# PoEpi_v2.net
KiCad netlist of a schematic drawn in EAGLE
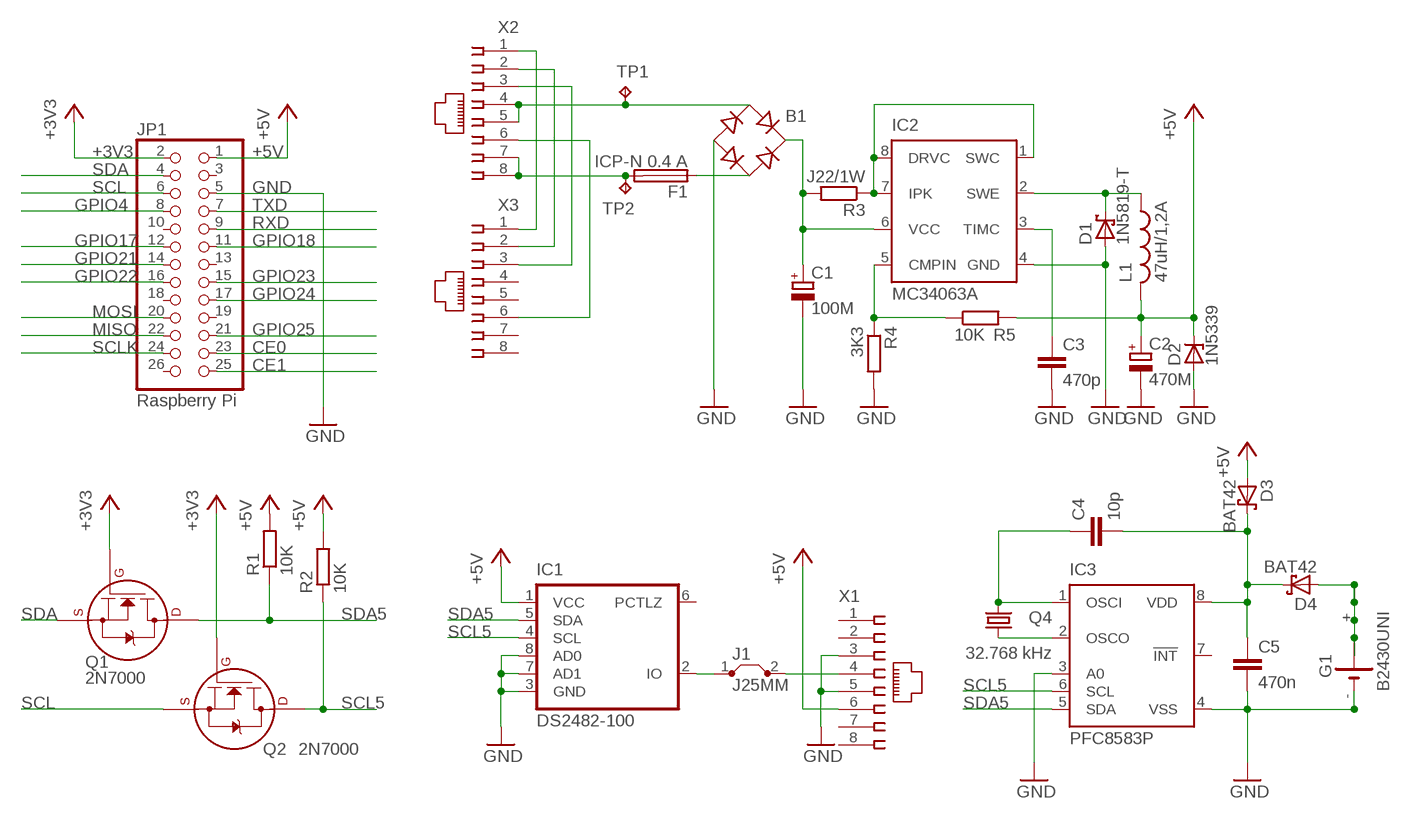
[diagram p0: schematic, sheet 1]

(export (version "E")
  (design (tool "Eeschema 10.0.6"))
  (components
    (comp (ref "B1")
      (value "B-DIL")
      (footprint "eagle-import:B-DIL")
      (libsource (lib "eagle-import") (part "B-DIL"))
    )
    (comp (ref "C1")
      (value "100M")
      (footprint "eagle-import:E3,5-8")
      (libsource (lib "eagle-import") (part "CPOL-EUE3.5-8"))
    )
    (comp (ref "C2")
      (value "470M")
      (footprint "eagle-import:E3,5-8")
      (libsource (lib "eagle-import") (part "CPOL-EUE3.5-8"))
    )
    (comp (ref "C3")
      (value "470p")
      (footprint "eagle-import:C050-024X044")
      (libsource (lib "eagle-import") (part "C-EU050-024X044"))
    )
    (comp (ref "C4")
      (value "10p")
      (footprint "eagle-import:C050-024X044")
      (libsource (lib "eagle-import") (part "C-EU050-024X044"))
    )
    (comp (ref "C5")
      (value "470n")
      (footprint "eagle-import:C050-024X044")
      (libsource (lib "eagle-import") (part "C-EU050-024X044"))
    )
    (comp (ref "D1")
      (value "1N5819-T")
      (footprint "eagle-import:DO41-7.6")
      (libsource (lib "eagle-import") (part "1N5819-T"))
    )
    (comp (ref "D2")
      (value "1N5339")
      (footprint "eagle-import:C1702-15")
      (libsource (lib "eagle-import") (part "1N5333"))
    )
    (comp (ref "D3")
      (value "BAT42")
      (footprint "eagle-import:DO35-10")
      (libsource (lib "eagle-import") (part "BAT42"))
    )
    (comp (ref "D4")
      (value "BAT42")
      (footprint "eagle-import:DO35-10")
      (libsource (lib "eagle-import") (part "BAT42"))
    )
    (comp (ref "F1")
      (value "ICP-N 0.4 A")
      (footprint "eagle-import:TO92-2")
      (libsource (lib "eagle-import") (part "FUSETO92-2"))
    )
    (comp (ref "G1")
      (value "B2430UNI")
      (footprint "eagle-import:B2430UNI")
      (libsource (lib "eagle-import") (part "B2430UNI"))
    )
    (comp (ref "IC1")
      (value "DS2482-100")
      (footprint "eagle-import:SO08")
      (libsource (lib "eagle-import") (part "DS2482-100"))
    )
    (comp (ref "IC2")
      (value "MC34063A")
      (footprint "eagle-import:DIL8")
      (libsource (lib "eagle-import") (part "MC34063A"))
    )
    (comp (ref "IC3")
      (value "PFC8583P")
      (footprint "eagle-import:DIL08")
      (libsource (lib "eagle-import") (part "PFC8583P"))
    )
    (comp (ref "J1")
      (value "J25MM")
      (footprint "eagle-import:25")
      (libsource (lib "eagle-import") (part "J25MM"))
    )
    (comp (ref "JP1")
      (value "Raspberry Pi")
      (footprint "eagle-import:2X13")
      (libsource (lib "eagle-import") (part "PINHD-2X13INV"))
    )
    (comp (ref "L1")
      (value "47uH/1,2A")
      (footprint "eagle-import:6000-XXXX-RC")
      (libsource (lib "eagle-import") (part "L-US6000-XXX-RC"))
    )
    (comp (ref "Q1")
      (value "2N7000")
      (footprint "eagle-import:TO92-")
      (libsource (lib "eagle-import") (part "2N700_TO92-"))
    )
    (comp (ref "Q2")
      (value "2N7000")
      (footprint "eagle-import:TO92-")
      (libsource (lib "eagle-import") (part "2N700_TO92-"))
    )
    (comp (ref "Q4")
      (value "32.768 kHz")
      (footprint "eagle-import:TC26V")
      (libsource (lib "eagle-import") (part "CRYSTALTC26V"))
    )
    (comp (ref "R1")
      (value "10K")
      (footprint "eagle-import:0204_7")
      (libsource (lib "eagle-import") (part "R-EU_0204/7"))
    )
    (comp (ref "R2")
      (value "10K")
      (footprint "eagle-import:0204_7")
      (libsource (lib "eagle-import") (part "R-EU_0204/7"))
    )
    (comp (ref "R3")
      (value "J22/1W")
      (footprint "eagle-import:0617_17")
      (libsource (lib "eagle-import") (part "R-EU_0617/17"))
    )
    (comp (ref "R4")
      (value "3K3")
      (footprint "eagle-import:0204_7")
      (libsource (lib "eagle-import") (part "R-EU_0204/7"))
    )
    (comp (ref "R5")
      (value "10K")
      (footprint "eagle-import:0204_7")
      (libsource (lib "eagle-import") (part "R-EU_0204/7"))
    )
    (comp (ref "TP1")
      (value "TPPAD1-13Y")
      (footprint "eagle-import:P1-13Y")
      (libsource (lib "eagle-import") (part "TPPAD1-13Y"))
    )
    (comp (ref "TP2")
      (value "TPPAD1-13Y")
      (footprint "eagle-import:P1-13Y")
      (libsource (lib "eagle-import") (part "TPPAD1-13Y"))
    )
    (comp (ref "X1")
      (value "520251-4")
      (footprint "eagle-import:520251-4")
      (libsource (lib "eagle-import") (part "520251-4"))
    )
    (comp (ref "X2")
      (value "520251-4")
      (footprint "eagle-import:520251-4")
      (libsource (lib "eagle-import") (part "520251-4"))
    )
    (comp (ref "X3")
      (value "520251-4")
      (footprint "eagle-import:520251-4")
      (libsource (lib "eagle-import") (part "520251-4"))
    )
  )
  (nets
    (net (code "1") (name "+3V3") (class "Default")
      (node (ref "JP1") (pin "2") (pinfunction "1_2") (pintype "passive"))
      (node (ref "Q1") (pin "2") (pinfunction "G_2") (pintype "tri_state"))
      (node (ref "Q2") (pin "2") (pinfunction "G_2") (pintype "tri_state"))
    )
    (net (code "2") (name "+5V") (class "Default")
      (node (ref "C2") (pin "+") (pinfunction "+_+") (pintype "passive"))
      (node (ref "D2") (pin "C") (pinfunction "C_C") (pintype "passive"))
      (node (ref "D3") (pin "A") (pinfunction "A_A") (pintype "passive"))
      (node (ref "IC1") (pin "1") (pinfunction "VCC_1") (pintype "power_in"))
      (node (ref "JP1") (pin "1") (pinfunction "2_1") (pintype "passive"))
      (node (ref "L1") (pin "2") (pinfunction "2_2") (pintype "passive"))
      (node (ref "R1") (pin "2") (pinfunction "2_2") (pintype "passive"))
      (node (ref "R2") (pin "2") (pinfunction "2_2") (pintype "passive"))
      (node (ref "R5") (pin "2") (pinfunction "2_2") (pintype "passive"))
      (node (ref "X1") (pin "6") (pinfunction "6_6") (pintype "passive"))
    )
    (net (code "3") (name "/CE0") (class "Default")
      (node (ref "JP1") (pin "23") (pinfunction "24_23") (pintype "passive"))
    )
    (net (code "4") (name "/CE1") (class "Default")
      (node (ref "JP1") (pin "25") (pinfunction "26_25") (pintype "passive"))
    )
    (net (code "5") (name "/GPIO4") (class "Default")
      (node (ref "JP1") (pin "8") (pinfunction "7_8") (pintype "passive"))
    )
    (net (code "6") (name "/GPIO17") (class "Default")
      (node (ref "JP1") (pin "12") (pinfunction "11_12") (pintype "passive"))
    )
    (net (code "7") (name "/GPIO18") (class "Default")
      (node (ref "JP1") (pin "11") (pinfunction "12_11") (pintype "passive"))
    )
    (net (code "8") (name "/GPIO21") (class "Default")
      (node (ref "JP1") (pin "14") (pinfunction "13_14") (pintype "passive"))
    )
    (net (code "9") (name "/GPIO22") (class "Default")
      (node (ref "JP1") (pin "16") (pinfunction "15_16") (pintype "passive"))
    )
    (net (code "10") (name "/GPIO23") (class "Default")
      (node (ref "JP1") (pin "15") (pinfunction "16_15") (pintype "passive"))
    )
    (net (code "11") (name "/GPIO24") (class "Default")
      (node (ref "JP1") (pin "17") (pinfunction "18_17") (pintype "passive"))
    )
    (net (code "12") (name "/GPIO25") (class "Default")
      (node (ref "JP1") (pin "21") (pinfunction "22_21") (pintype "passive"))
    )
    (net (code "13") (name "/MISO") (class "Default")
      (node (ref "JP1") (pin "22") (pinfunction "21_22") (pintype "passive"))
    )
    (net (code "14") (name "/MOSI") (class "Default")
      (node (ref "JP1") (pin "20") (pinfunction "19_20") (pintype "passive"))
    )
    (net (code "15") (name "/RXD") (class "Default")
      (node (ref "JP1") (pin "9") (pinfunction "10_9") (pintype "passive"))
    )
    (net (code "16") (name "/SCL") (class "Default")
      (node (ref "JP1") (pin "6") (pinfunction "5_6") (pintype "passive"))
      (node (ref "Q2") (pin "3") (pinfunction "S_3") (pintype "bidirectional"))
    )
    (net (code "17") (name "/SCL5") (class "Default")
      (node (ref "IC1") (pin "4") (pinfunction "SCL_4") (pintype "input"))
      (node (ref "IC3") (pin "6") (pinfunction "SCL_6") (pintype "input"))
      (node (ref "Q2") (pin "1") (pinfunction "D_1") (pintype "bidirectional"))
      (node (ref "R2") (pin "1") (pinfunction "1_1") (pintype "passive"))
    )
    (net (code "18") (name "/SCLK") (class "Default")
      (node (ref "JP1") (pin "24") (pinfunction "23_24") (pintype "passive"))
    )
    (net (code "19") (name "/SDA") (class "Default")
      (node (ref "JP1") (pin "4") (pinfunction "3_4") (pintype "passive"))
      (node (ref "Q1") (pin "3") (pinfunction "S_3") (pintype "bidirectional"))
    )
    (net (code "20") (name "/SDA5") (class "Default")
      (node (ref "IC1") (pin "5") (pinfunction "SDA_5") (pintype "input"))
      (node (ref "IC3") (pin "5") (pinfunction "SDA_5") (pintype "bidirectional"))
      (node (ref "Q1") (pin "1") (pinfunction "D_1") (pintype "bidirectional"))
      (node (ref "R1") (pin "1") (pinfunction "1_1") (pintype "passive"))
    )
    (net (code "21") (name "/TXD") (class "Default")
      (node (ref "JP1") (pin "7") (pinfunction "8_7") (pintype "passive"))
    )
    (net (code "22") (name "GND") (class "Default")
      (node (ref "B1") (pin "-") (pinfunction "-_-") (pintype "passive"))
      (node (ref "C1") (pin "-") (pinfunction "-_-") (pintype "passive"))
      (node (ref "C2") (pin "-") (pinfunction "-_-") (pintype "passive"))
      (node (ref "C3") (pin "2") (pinfunction "2_2") (pintype "passive"))
      (node (ref "C5") (pin "2") (pinfunction "2_2") (pintype "passive"))
      (node (ref "D1") (pin "A") (pinfunction "A_A") (pintype "passive"))
      (node (ref "D2") (pin "A") (pinfunction "A_A") (pintype "passive"))
      (node (ref "G1") (pin "-") (pinfunction "-_-") (pintype "passive"))
      (node (ref "G1") (pin "-@1") (pinfunction "-_-@1") (pintype "passive"))
      (node (ref "IC1") (pin "3") (pinfunction "GND_3") (pintype "power_in"))
      (node (ref "IC1") (pin "7") (pinfunction "AD1_7") (pintype "bidirectional"))
      (node (ref "IC1") (pin "8") (pinfunction "AD0_8") (pintype "bidirectional"))
      (node (ref "IC2") (pin "4") (pinfunction "GND_4") (pintype "power_in"))
      (node (ref "IC3") (pin "3") (pinfunction "A0_3") (pintype "input"))
      (node (ref "IC3") (pin "4") (pinfunction "VSS_4") (pintype "power_in"))
      (node (ref "JP1") (pin "5") (pinfunction "6_5") (pintype "passive"))
      (node (ref "R4") (pin "2") (pinfunction "2_2") (pintype "passive"))
      (node (ref "X1") (pin "3") (pinfunction "3_3") (pintype "passive"))
      (node (ref "X1") (pin "5") (pinfunction "5_5") (pintype "passive"))
    )
    (net (code "23") (name "Net-(B1-PadAC1)") (class "Default")
      (node (ref "B1") (pin "AC1") (pinfunction "AC1_AC1") (pintype "passive"))
      (node (ref "TP1") (pin "TP") (pinfunction "TP_TP") (pintype "input"))
      (node (ref "X2") (pin "4") (pinfunction "4_4") (pintype "passive"))
      (node (ref "X2") (pin "5") (pinfunction "5_5") (pintype "passive"))
    )
    (net (code "24") (name "Net-(B1-PadAC2)") (class "Default")
      (node (ref "B1") (pin "AC2") (pinfunction "AC2_AC2") (pintype "passive"))
      (node (ref "F1") (pin "1") (pinfunction "1_1") (pintype "passive"))
    )
    (net (code "25") (name "Net-(D4-PadA)") (class "Default")
      (node (ref "D4") (pin "A") (pinfunction "A_A") (pintype "passive"))
      (node (ref "G1") (pin "+") (pinfunction "+_+") (pintype "passive"))
      (node (ref "G1") (pin "+@1") (pinfunction "+_+@1") (pintype "passive"))
      (node (ref "G1") (pin "+@2") (pinfunction "+_+@2") (pintype "passive"))
      (node (ref "G1") (pin "+@3") (pinfunction "+_+@3") (pintype "passive"))
      (node (ref "G1") (pin "+@4") (pinfunction "+_+@4") (pintype "passive"))
    )
    (net (code "26") (name "Net-(F1-2)") (class "Default")
      (node (ref "F1") (pin "3") (pinfunction "2_3") (pintype "passive"))
      (node (ref "TP2") (pin "TP") (pinfunction "TP_TP") (pintype "input"))
      (node (ref "X2") (pin "7") (pinfunction "7_7") (pintype "passive"))
      (node (ref "X2") (pin "8") (pinfunction "8_8") (pintype "passive"))
    )
    (net (code "27") (name "Net-(IC1-IO)") (class "Default")
      (node (ref "IC1") (pin "2") (pinfunction "IO_2") (pintype "bidirectional"))
      (node (ref "J1") (pin "1") (pinfunction "1_1") (pintype "passive"))
    )
    (net (code "28") (name "Net-(IC2-CMPIN)") (class "Default")
      (node (ref "IC2") (pin "5") (pinfunction "CMPIN_5") (pintype "input"))
      (node (ref "R4") (pin "1") (pinfunction "1_1") (pintype "passive"))
      (node (ref "R5") (pin "1") (pinfunction "1_1") (pintype "passive"))
    )
    (net (code "29") (name "Net-(IC2-DRVC)") (class "Default")
      (node (ref "IC2") (pin "1") (pinfunction "SWC_1") (pintype "open_collector"))
      (node (ref "IC2") (pin "7") (pinfunction "IPK_7") (pintype "input"))
      (node (ref "IC2") (pin "8") (pinfunction "DRVC_8") (pintype "input"))
      (node (ref "R3") (pin "1") (pinfunction "1_1") (pintype "passive"))
    )
    (net (code "30") (name "Net-(IC2-SWE)") (class "Default")
      (node (ref "D1") (pin "C") (pinfunction "C_C") (pintype "passive"))
      (node (ref "IC2") (pin "2") (pinfunction "SWE_2") (pintype "output"))
      (node (ref "L1") (pin "1") (pinfunction "1_1") (pintype "passive"))
    )
    (net (code "31") (name "Net-(IC2-TIMC)") (class "Default")
      (node (ref "C3") (pin "1") (pinfunction "1_1") (pintype "passive"))
      (node (ref "IC2") (pin "3") (pinfunction "TIMC_3") (pintype "output"))
    )
    (net (code "32") (name "Net-(IC2-VCC)") (class "Default")
      (node (ref "B1") (pin "+") (pinfunction "+_+") (pintype "passive"))
      (node (ref "C1") (pin "+") (pinfunction "+_+") (pintype "passive"))
      (node (ref "IC2") (pin "6") (pinfunction "VCC_6") (pintype "power_in"))
      (node (ref "R3") (pin "2") (pinfunction "2_2") (pintype "passive"))
    )
    (net (code "33") (name "Net-(IC3-OSCI)") (class "Default")
      (node (ref "C4") (pin "1") (pinfunction "1_1") (pintype "passive"))
      (node (ref "IC3") (pin "1") (pinfunction "OSCI_1") (pintype "input"))
      (node (ref "Q4") (pin "2") (pinfunction "2_2") (pintype "passive"))
    )
    (net (code "34") (name "Net-(IC3-OSCO)") (class "Default")
      (node (ref "IC3") (pin "2") (pinfunction "OSCO_2") (pintype "output"))
      (node (ref "Q4") (pin "1") (pinfunction "1_1") (pintype "passive"))
    )
    (net (code "35") (name "Net-(IC3-VDD)") (class "Default")
      (node (ref "C4") (pin "2") (pinfunction "2_2") (pintype "passive"))
      (node (ref "C5") (pin "1") (pinfunction "1_1") (pintype "passive"))
      (node (ref "D3") (pin "C") (pinfunction "C_C") (pintype "passive"))
      (node (ref "D4") (pin "C") (pinfunction "C_C") (pintype "passive"))
      (node (ref "IC3") (pin "8") (pinfunction "VDD_8") (pintype "power_in"))
    )
    (net (code "36") (name "Net-(J1-Pad2)") (class "Default")
      (node (ref "J1") (pin "2") (pinfunction "2_2") (pintype "passive"))
      (node (ref "X1") (pin "4") (pinfunction "4_4") (pintype "passive"))
    )
    (net (code "37") (name "Net-(X2-Pad1)") (class "Default")
      (node (ref "X2") (pin "1") (pinfunction "1_1") (pintype "passive"))
      (node (ref "X3") (pin "1") (pinfunction "1_1") (pintype "passive"))
    )
    (net (code "38") (name "Net-(X2-Pad2)") (class "Default")
      (node (ref "X2") (pin "2") (pinfunction "2_2") (pintype "passive"))
      (node (ref "X3") (pin "2") (pinfunction "2_2") (pintype "passive"))
    )
    (net (code "39") (name "Net-(X2-Pad3)") (class "Default")
      (node (ref "X2") (pin "3") (pinfunction "3_3") (pintype "passive"))
      (node (ref "X3") (pin "3") (pinfunction "3_3") (pintype "passive"))
    )
    (net (code "40") (name "Net-(X2-Pad6)") (class "Default")
      (node (ref "X2") (pin "6") (pinfunction "6_6") (pintype "passive"))
      (node (ref "X3") (pin "6") (pinfunction "6_6") (pintype "passive"))
    )
    (net (code "41") (name "unconnected-(IC1-PCTLZ-Pad6)") (class "Default")
      (node (ref "IC1") (pin "6") (pinfunction "PCTLZ_6") (pintype "output"))
    )
    (net (code "42") (name "unconnected-(IC3-~{INT}-Pad7)") (class "Default")
      (node (ref "IC3") (pin "7") (pinfunction "~{INT}_7") (pintype "output"))
    )
    (net (code "43") (name "unconnected-(JP1-4-Pad3)") (class "Default")
      (node (ref "JP1") (pin "3") (pinfunction "4_3") (pintype "passive"))
    )
    (net (code "44") (name "unconnected-(JP1-9-Pad10)") (class "Default")
      (node (ref "JP1") (pin "10") (pinfunction "9_10") (pintype "passive"))
    )
    (net (code "45") (name "unconnected-(JP1-14-Pad13)") (class "Default")
      (node (ref "JP1") (pin "13") (pinfunction "14_13") (pintype "passive"))
    )
    (net (code "46") (name "unconnected-(JP1-17-Pad18)") (class "Default")
      (node (ref "JP1") (pin "18") (pinfunction "17_18") (pintype "passive"))
    )
    (net (code "47") (name "unconnected-(JP1-20-Pad19)") (class "Default")
      (node (ref "JP1") (pin "19") (pinfunction "20_19") (pintype "passive"))
    )
    (net (code "48") (name "unconnected-(JP1-25-Pad26)") (class "Default")
      (node (ref "JP1") (pin "26") (pinfunction "25_26") (pintype "passive"))
    )
    (net (code "49") (name "unconnected-(X1-Pad1)") (class "Default")
      (node (ref "X1") (pin "1") (pinfunction "1_1") (pintype "passive"))
    )
    (net (code "50") (name "unconnected-(X1-Pad2)") (class "Default")
      (node (ref "X1") (pin "2") (pinfunction "2_2") (pintype "passive"))
    )
    (net (code "51") (name "unconnected-(X1-Pad7)") (class "Default")
      (node (ref "X1") (pin "7") (pinfunction "7_7") (pintype "passive"))
    )
    (net (code "52") (name "unconnected-(X1-Pad8)") (class "Default")
      (node (ref "X1") (pin "8") (pinfunction "8_8") (pintype "passive"))
    )
    (net (code "53") (name "unconnected-(X3-Pad4)") (class "Default")
      (node (ref "X3") (pin "4") (pinfunction "4_4") (pintype "passive"))
    )
    (net (code "54") (name "unconnected-(X3-Pad5)") (class "Default")
      (node (ref "X3") (pin "5") (pinfunction "5_5") (pintype "passive"))
    )
    (net (code "55") (name "unconnected-(X3-Pad7)") (class "Default")
      (node (ref "X3") (pin "7") (pinfunction "7_7") (pintype "passive"))
    )
    (net (code "56") (name "unconnected-(X3-Pad8)") (class "Default")
      (node (ref "X3") (pin "8") (pinfunction "8_8") (pintype "passive"))
    )
  )
)
